# PWR.net
KiCad netlist of a schematic drawn in Altium Designer
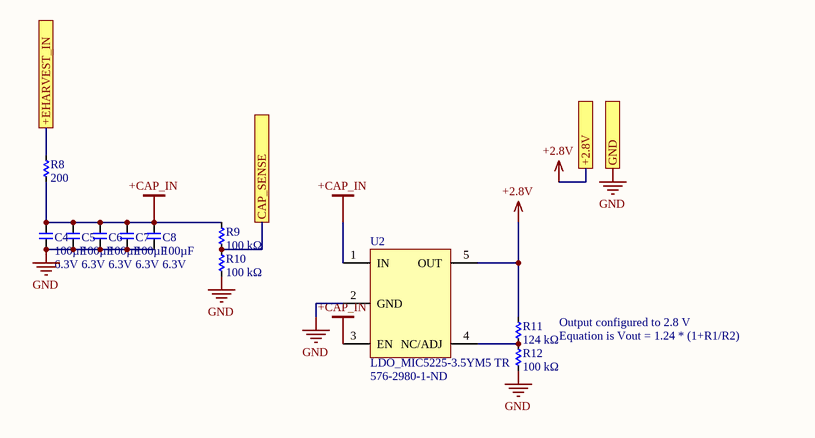
[diagram p0: PWR.SchDoc]

(export (version "E")
  (design (tool "Eeschema 10.0.6"))
  (components
    (comp (ref "C4")
      (value "CAP_100UF_1206_SMD")
      (footprint "C1206")
      (description "100UF SMD CAP CERAMIC")
      (fields
        (field (name "MANUFACTURER") "Murata Electronics North America")
        (field (name "MANUFACTURER PART NUMBER") "GRM31CD80J107ME39L")
        (field (name "CAPACITANCE") "100µF")
        (field (name "VOLTAGE - RATED") "6.3V")
      )
      (libsource (lib "SSI") (part "CAP_100UF_1206_SMD"))
    )
    (comp (ref "C5")
      (value "CAP_100UF_1206_SMD")
      (footprint "C1206")
      (description "100UF SMD CAP CERAMIC")
      (fields
        (field (name "MANUFACTURER") "Murata Electronics North America")
        (field (name "MANUFACTURER PART NUMBER") "GRM31CD80J107ME39L")
        (field (name "CAPACITANCE") "100µF")
        (field (name "VOLTAGE - RATED") "6.3V")
      )
      (libsource (lib "SSI") (part "CAP_100UF_1206_SMD"))
    )
    (comp (ref "C6")
      (value "CAP_100UF_1206_SMD")
      (footprint "C1206")
      (description "100UF SMD CAP CERAMIC")
      (fields
        (field (name "MANUFACTURER") "Murata Electronics North America")
        (field (name "MANUFACTURER PART NUMBER") "GRM31CD80J107ME39L")
        (field (name "CAPACITANCE") "100µF")
        (field (name "VOLTAGE - RATED") "6.3V")
      )
      (libsource (lib "SSI") (part "CAP_100UF_1206_SMD"))
    )
    (comp (ref "C7")
      (value "CAP_100UF_1206_SMD")
      (footprint "C1206")
      (description "100UF SMD CAP CERAMIC")
      (fields
        (field (name "MANUFACTURER") "Murata Electronics North America")
        (field (name "MANUFACTURER PART NUMBER") "GRM31CD80J107ME39L")
        (field (name "CAPACITANCE") "100µF")
        (field (name "VOLTAGE - RATED") "6.3V")
      )
      (libsource (lib "SSI") (part "CAP_100UF_1206_SMD"))
    )
    (comp (ref "C8")
      (value "CAP_100UF_1206_SMD")
      (footprint "C1206")
      (description "100UF SMD CAP CERAMIC")
      (fields
        (field (name "MANUFACTURER") "Murata Electronics North America")
        (field (name "MANUFACTURER PART NUMBER") "GRM31CD80J107ME39L")
        (field (name "CAPACITANCE") "100µF")
        (field (name "VOLTAGE - RATED") "6.3V")
      )
      (libsource (lib "SSI") (part "CAP_100UF_1206_SMD"))
    )
    (comp (ref "R8")
      (value "200")
      (footprint "R1206")
      (fields
        (field (name "MANUFACTURER PART NUMBER") "CRCW1206200RFKEA")
        (field (name "MANUFACTURER") "Vishay Dale")
        (field (name "TOLERANCE") "±1%")
      )
      (libsource (lib "resistor") (part "__template_resistor"))
    )
    (comp (ref "R9")
      (value "__template_resistor")
      (footprint "R0805")
      (fields
        (field (name "RESISTANCE") "100 kΩ")
        (field (name "MANUFACTURER PART NUMBER") "RC0805FR-07100KL")
        (field (name "MANUFACTURER") "Yageo")
        (field (name "TOLERANCE") "±1%")
      )
      (libsource (lib "passives") (part "__template_resistor"))
    )
    (comp (ref "R10")
      (value "__template_resistor")
      (footprint "R0805")
      (fields
        (field (name "RESISTANCE") "100 kΩ")
        (field (name "MANUFACTURER PART NUMBER") "RC0805FR-07100KL")
        (field (name "MANUFACTURER") "Yageo")
        (field (name "TOLERANCE") "±1%")
      )
      (libsource (lib "passives") (part "__template_resistor"))
    )
    (comp (ref "R11")
      (value "__template_resistor")
      (footprint "R0805")
      (fields
        (field (name "RESISTANCE") "124 kΩ")
        (field (name "MANUFACTURER PART NUMBER") "RC0805FR-07124KL")
        (field (name "MANUFACTURER") "Yageo")
        (field (name "TOLERANCE") "±1%")
      )
      (libsource (lib "passives") (part "__template_resistor"))
    )
    (comp (ref "R12")
      (value "__template_resistor")
      (footprint "R0805")
      (fields
        (field (name "RESISTANCE") "100 kΩ")
        (field (name "MANUFACTURER PART NUMBER") "RC0805FR-07100KL")
        (field (name "MANUFACTURER") "Yageo")
        (field (name "TOLERANCE") "±1%")
      )
      (libsource (lib "passives") (part "__template_resistor"))
    )
    (comp (ref "U2")
      (value "LDO_MIC5225-3.5YM5 TR")
      (footprint "5SOT23")
      (description "IC REG LINEAR 3.3V 150MA SOT23-5")
      (fields
        (field (name "MANUFACTURER") "Microchip Technology")
        (field (name "MANUFACTURER PART NUMBER") "MIC5225-3.3YM5-TR")
        (field (name "SUPPLIER PART NUMBER 1") "576-2980-1-ND")
      )
      (libsource (lib "SSI") (part "LDO_MIC5225-3.5YM5 TR"))
    )
  )
  (nets
    (net (code "1") (name "+2.8V") (class "Default")
      (node (ref "R11") (pin "2") (pintype "passive"))
      (node (ref "U2") (pin "5") (pinfunction "OUT_5") (pintype "power_in"))
    )
    (net (code "2") (name "+CAP_IN") (class "Default")
      (node (ref "C4") (pin "1") (pintype "passive"))
      (node (ref "C5") (pin "1") (pintype "passive"))
      (node (ref "C6") (pin "1") (pintype "passive"))
      (node (ref "C7") (pin "1") (pintype "passive"))
      (node (ref "C8") (pin "1") (pintype "passive"))
      (node (ref "R8") (pin "1") (pintype "passive"))
      (node (ref "R9") (pin "2") (pintype "passive"))
      (node (ref "U2") (pin "1") (pinfunction "IN_1") (pintype "power_in"))
      (node (ref "U2") (pin "3") (pinfunction "EN_3") (pintype "power_in"))
    )
    (net (code "3") (name "/+EHARVEST_IN") (class "Default") (node (ref "R8") (pin "2") (pintype "passive")))
    (net (code "4") (name "/CAP_SENSE") (class "Default")
      (node (ref "R10") (pin "2") (pintype "passive"))
      (node (ref "R9") (pin "1") (pintype "passive"))
    )
    (net (code "5") (name "GND") (class "Default")
      (node (ref "C4") (pin "2") (pintype "passive"))
      (node (ref "C5") (pin "2") (pintype "passive"))
      (node (ref "C6") (pin "2") (pintype "passive"))
      (node (ref "C7") (pin "2") (pintype "passive"))
      (node (ref "C8") (pin "2") (pintype "passive"))
      (node (ref "R10") (pin "1") (pintype "passive"))
      (node (ref "R12") (pin "2") (pintype "passive"))
      (node (ref "U2") (pin "2") (pinfunction "GND_2") (pintype "power_in"))
    )
    (net (code "6") (name "Net-(U2-NC{slash}ADJ)") (class "Default")
      (node (ref "R11") (pin "1") (pintype "passive"))
      (node (ref "R12") (pin "1") (pintype "passive"))
      (node (ref "U2") (pin "4") (pinfunction "NC/ADJ_4") (pintype "power_in"))
    )
  )
)
